# Kasil_DIOT_x86_board.net
KiCad netlist of a schematic drawn in Altium Designer
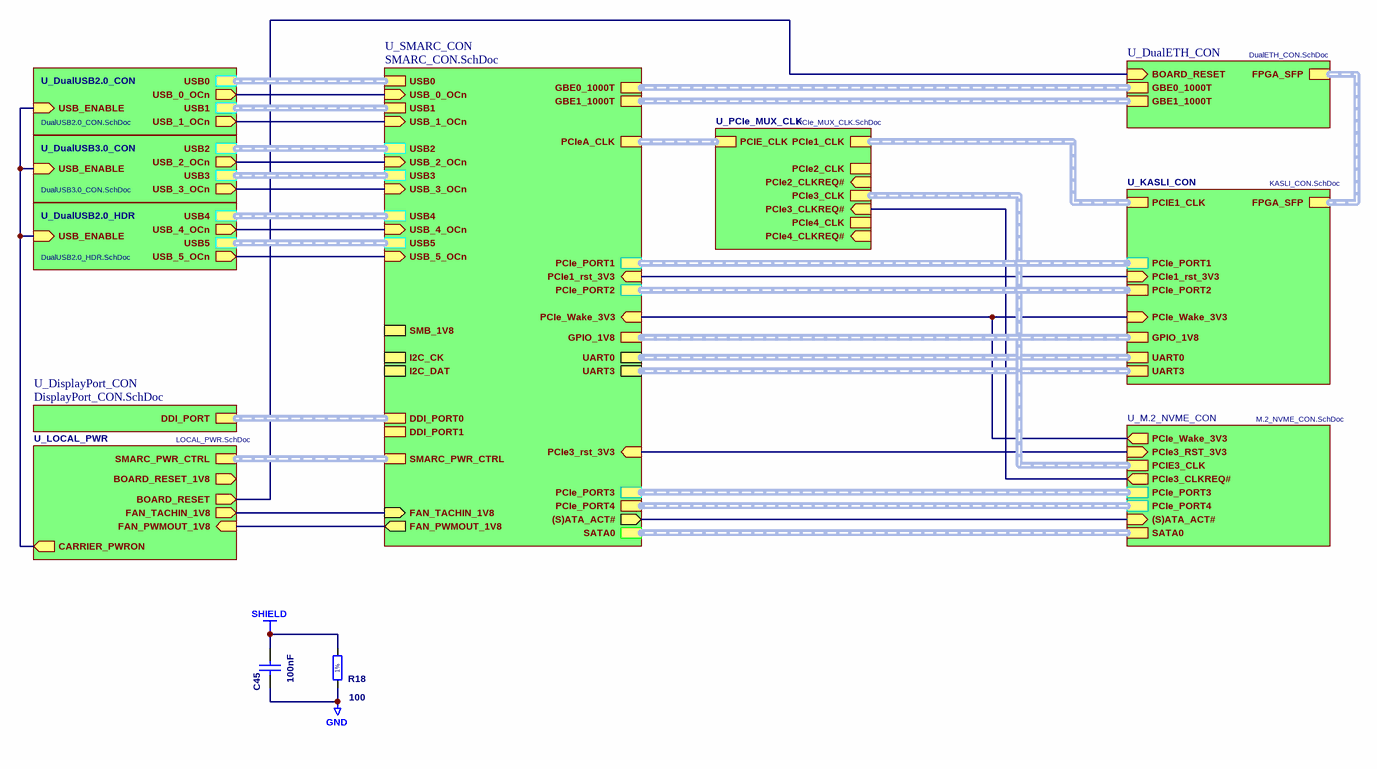
[diagram p0: Kasil_DIOT_x86_board.SchDoc]

(export (version "E")
  (design (tool "Eeschema 10.0.6"))
  (components
    (comp (ref "C45")
      (value "100nF")
      (footprint "CAPC1005X55N")
      (description "Non-polarised capacitor")
      (fields
        (field (name "PART NUMBER") "CC0402_100NF_16V_10%_X7R")
        (field (name "VOLTAGE") "16V")
        (field (name "AUTHOR") "CERN DEM JLC")
      )
      (libsource (lib "Capacitors") (part "Capacitor - non polarized"))
    )
    (comp (ref "R18")
      (value "100")
      (footprint "RESC1005X40N")
      (description "Resistor - 1%")
      (fields
        (field (name "PART NUMBER") "R0402_100R_1%_0.0625W_100PPM")
        (field (name "POWER") "0.0625W")
        (field (name "AUTHOR") "CERN DEM JLC")
      )
      (libsource (lib "Resistors") (part "Resistor - 1%"))
    )
  )
  (nets
    (net (code "47") (name "GND") (class "Default")
      (node (ref "C45") (pin "1") (pinfunction "1_1") (pintype "passive"))
      (node (ref "R18") (pin "1") (pinfunction "1_1") (pintype "passive"))
    )
    (net (code "48") (name "SHIELD") (class "Default")
      (node (ref "C45") (pin "2") (pinfunction "2_2") (pintype "passive"))
      (node (ref "R18") (pin "2") (pinfunction "2_2") (pintype "passive"))
    )
  )
)
